# W026B.net
KiCad netlist of a schematic drawn in EAGLE
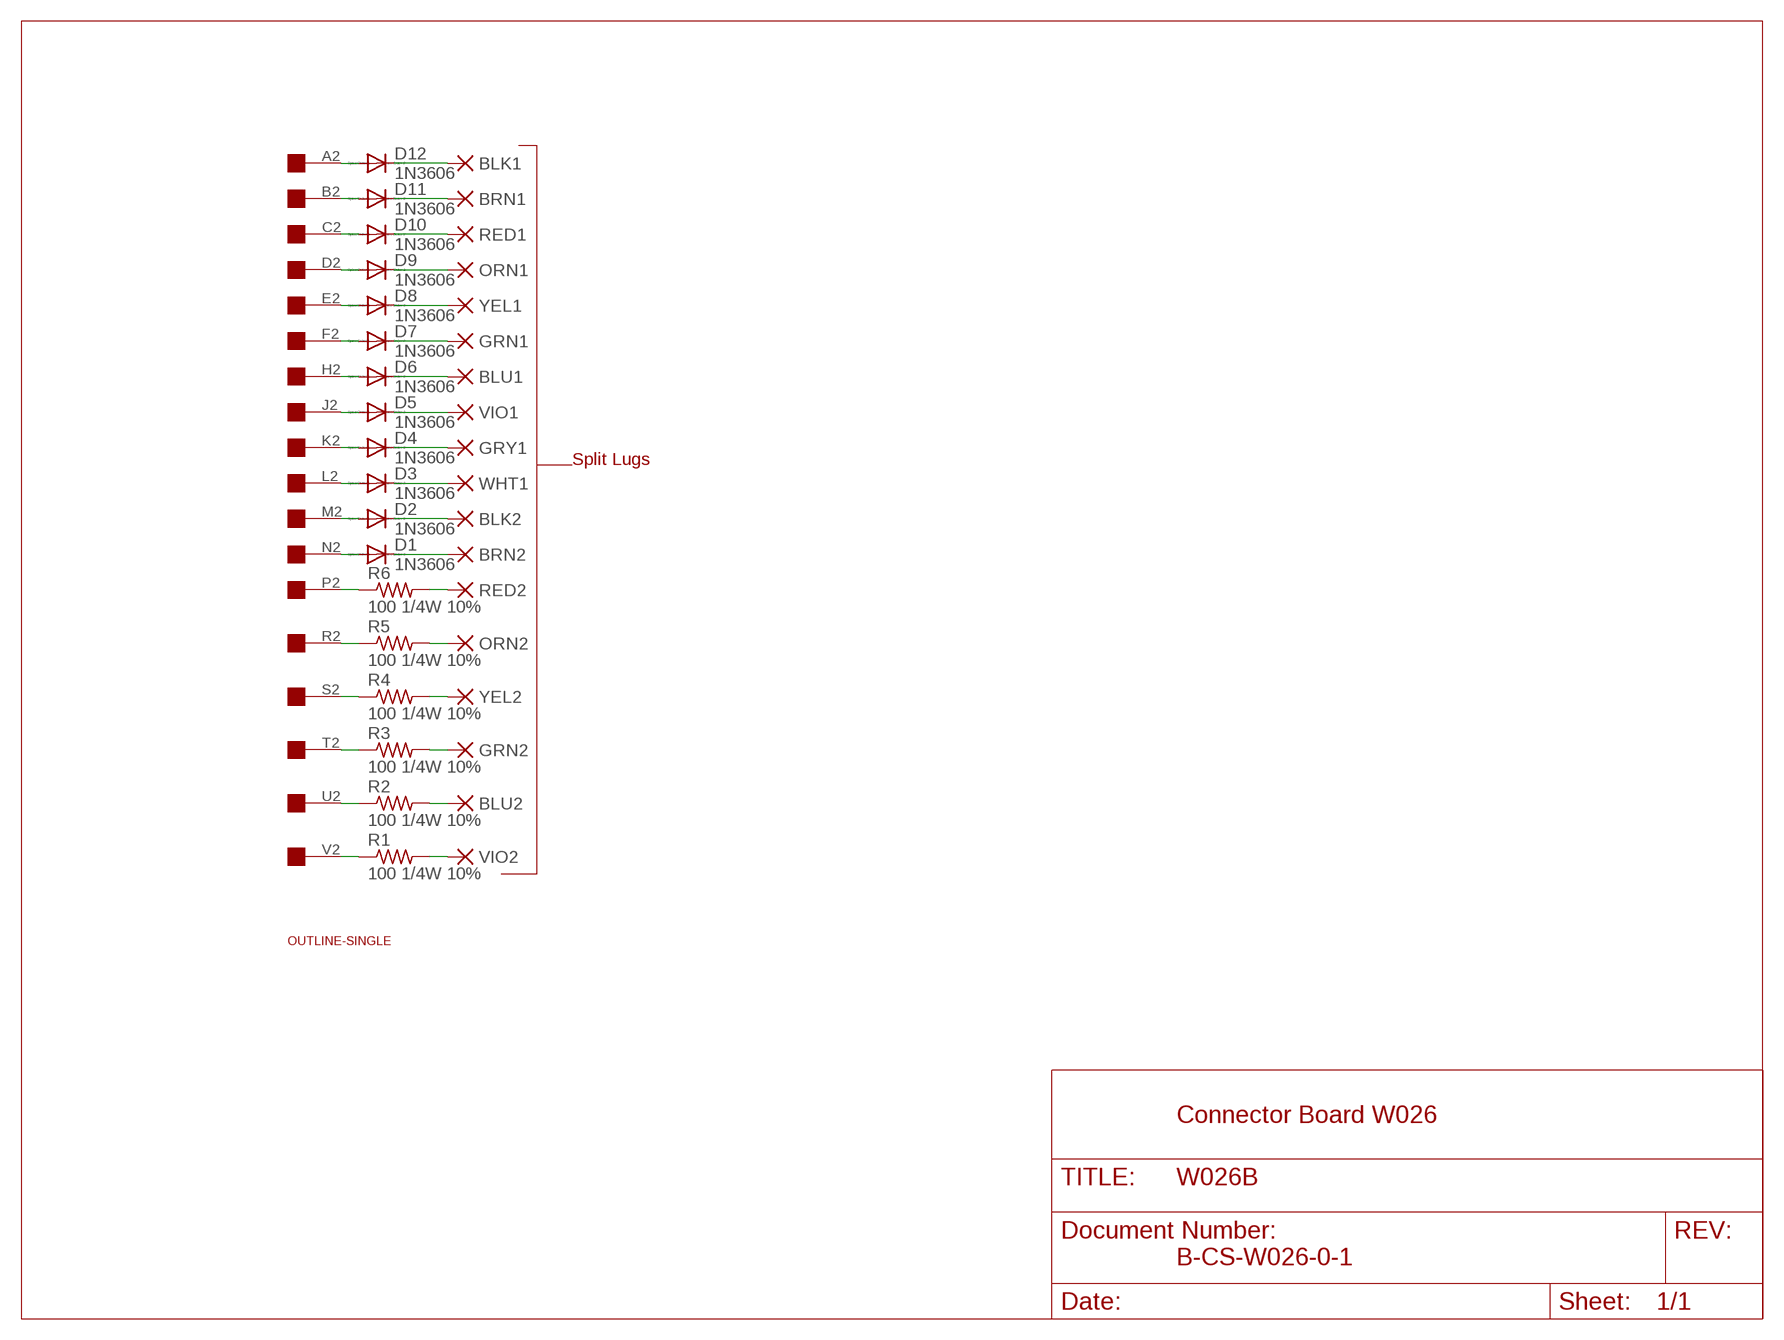
[diagram p0: schematic, sheet 1]

(export (version "E")
  (design (tool "Eeschema 10.0.6"))
  (components
    (comp (ref "BLK1")
      (value "PAD-0465")
      (footprint "eagle-import:0465")
      (libsource (lib "eagle-import") (part "PAD-0465"))
    )
    (comp (ref "BLK2")
      (value "PAD-0465")
      (footprint "eagle-import:0465")
      (libsource (lib "eagle-import") (part "PAD-0465"))
    )
    (comp (ref "BLU1")
      (value "PAD-0465")
      (footprint "eagle-import:0465")
      (libsource (lib "eagle-import") (part "PAD-0465"))
    )
    (comp (ref "BLU2")
      (value "PAD-0465")
      (footprint "eagle-import:0465")
      (libsource (lib "eagle-import") (part "PAD-0465"))
    )
    (comp (ref "BRN1")
      (value "PAD-0465")
      (footprint "eagle-import:0465")
      (libsource (lib "eagle-import") (part "PAD-0465"))
    )
    (comp (ref "BRN2")
      (value "PAD-0465")
      (footprint "eagle-import:0465")
      (libsource (lib "eagle-import") (part "PAD-0465"))
    )
    (comp (ref "D1")
      (value "1N3606")
      (footprint "eagle-import:DO35-10")
      (libsource (lib "eagle-import") (part "1N4148DO35-10"))
    )
    (comp (ref "D2")
      (value "1N3606")
      (footprint "eagle-import:DO35-10")
      (libsource (lib "eagle-import") (part "1N4148DO35-10"))
    )
    (comp (ref "D3")
      (value "1N3606")
      (footprint "eagle-import:DO35-10")
      (libsource (lib "eagle-import") (part "1N4148DO35-10"))
    )
    (comp (ref "D4")
      (value "1N3606")
      (footprint "eagle-import:DO35-10")
      (libsource (lib "eagle-import") (part "1N4148DO35-10"))
    )
    (comp (ref "D5")
      (value "1N3606")
      (footprint "eagle-import:DO35-10")
      (libsource (lib "eagle-import") (part "1N4148DO35-10"))
    )
    (comp (ref "D6")
      (value "1N3606")
      (footprint "eagle-import:DO35-10")
      (libsource (lib "eagle-import") (part "1N4148DO35-10"))
    )
    (comp (ref "D7")
      (value "1N3606")
      (footprint "eagle-import:DO35-10")
      (libsource (lib "eagle-import") (part "1N4148DO35-10"))
    )
    (comp (ref "D8")
      (value "1N3606")
      (footprint "eagle-import:DO35-10")
      (libsource (lib "eagle-import") (part "1N4148DO35-10"))
    )
    (comp (ref "D9")
      (value "1N3606")
      (footprint "eagle-import:DO35-10")
      (libsource (lib "eagle-import") (part "1N4148DO35-10"))
    )
    (comp (ref "D10")
      (value "1N3606")
      (footprint "eagle-import:DO35-10")
      (libsource (lib "eagle-import") (part "1N4148DO35-10"))
    )
    (comp (ref "D11")
      (value "1N3606")
      (footprint "eagle-import:DO35-10")
      (libsource (lib "eagle-import") (part "1N4148DO35-10"))
    )
    (comp (ref "D12")
      (value "1N3606")
      (footprint "eagle-import:DO35-10")
      (libsource (lib "eagle-import") (part "1N4148DO35-10"))
    )
    (comp (ref "GRN1")
      (value "PAD-0465")
      (footprint "eagle-import:0465")
      (libsource (lib "eagle-import") (part "PAD-0465"))
    )
    (comp (ref "GRN2")
      (value "PAD-0465")
      (footprint "eagle-import:0465")
      (libsource (lib "eagle-import") (part "PAD-0465"))
    )
    (comp (ref "GRY1")
      (value "PAD-0465")
      (footprint "eagle-import:0465")
      (libsource (lib "eagle-import") (part "PAD-0465"))
    )
    (comp (ref "ORN1")
      (value "PAD-0465")
      (footprint "eagle-import:0465")
      (libsource (lib "eagle-import") (part "PAD-0465"))
    )
    (comp (ref "ORN2")
      (value "PAD-0465")
      (footprint "eagle-import:0465")
      (libsource (lib "eagle-import") (part "PAD-0465"))
    )
    (comp (ref "R1")
      (value "100 1/4W 10%")
      (footprint "eagle-import:0207_10")
      (libsource (lib "eagle-import") (part "R-US_0207/10"))
    )
    (comp (ref "R2")
      (value "100 1/4W 10%")
      (footprint "eagle-import:0207_10")
      (libsource (lib "eagle-import") (part "R-US_0207/10"))
    )
    (comp (ref "R3")
      (value "100 1/4W 10%")
      (footprint "eagle-import:0207_10")
      (libsource (lib "eagle-import") (part "R-US_0207/10"))
    )
    (comp (ref "R4")
      (value "100 1/4W 10%")
      (footprint "eagle-import:0207_10")
      (libsource (lib "eagle-import") (part "R-US_0207/10"))
    )
    (comp (ref "R5")
      (value "100 1/4W 10%")
      (footprint "eagle-import:0207_10")
      (libsource (lib "eagle-import") (part "R-US_0207/10"))
    )
    (comp (ref "R6")
      (value "100 1/4W 10%")
      (footprint "eagle-import:0207_10")
      (libsource (lib "eagle-import") (part "R-US_0207/10"))
    )
    (comp (ref "RED1")
      (value "PAD-0465")
      (footprint "eagle-import:0465")
      (libsource (lib "eagle-import") (part "PAD-0465"))
    )
    (comp (ref "RED2")
      (value "PAD-0465")
      (footprint "eagle-import:0465")
      (libsource (lib "eagle-import") (part "PAD-0465"))
    )
    (comp (ref "U$1")
      (value "OUTLINE-SINGLE")
      (footprint "eagle-import:SINGLE")
      (libsource (lib "eagle-import") (part "OUTLINE-SINGLE"))
    )
    (comp (ref "U$2")
      (value "EDGE-1")
      (footprint "eagle-import:EDGE-CON1")
      (libsource (lib "eagle-import") (part "EDGE-1"))
    )
    (comp (ref "VIO1")
      (value "PAD-0465")
      (footprint "eagle-import:0465")
      (libsource (lib "eagle-import") (part "PAD-0465"))
    )
    (comp (ref "VIO2")
      (value "PAD-0465")
      (footprint "eagle-import:0465")
      (libsource (lib "eagle-import") (part "PAD-0465"))
    )
    (comp (ref "WHT1")
      (value "PAD-0465")
      (footprint "eagle-import:0465")
      (libsource (lib "eagle-import") (part "PAD-0465"))
    )
    (comp (ref "YEL1")
      (value "PAD-0465")
      (footprint "eagle-import:0465")
      (libsource (lib "eagle-import") (part "PAD-0465"))
    )
    (comp (ref "YEL2")
      (value "PAD-0465")
      (footprint "eagle-import:0465")
      (libsource (lib "eagle-import") (part "PAD-0465"))
    )
  )
  (nets
    (net (code "1") (name "Net-(BLK1-P)") (class "Default")
      (node (ref "BLK1") (pin "P$1") (pinfunction "P_P$1") (pintype "passive"))
      (node (ref "D12") (pin "C") (pinfunction "C_C") (pintype "passive"))
    )
    (net (code "2") (name "Net-(BLK2-P)") (class "Default")
      (node (ref "BLK2") (pin "P$1") (pinfunction "P_P$1") (pintype "passive"))
      (node (ref "D2") (pin "C") (pinfunction "C_C") (pintype "passive"))
    )
    (net (code "3") (name "Net-(BLU1-P)") (class "Default")
      (node (ref "BLU1") (pin "P$1") (pinfunction "P_P$1") (pintype "passive"))
      (node (ref "D6") (pin "C") (pinfunction "C_C") (pintype "passive"))
    )
    (net (code "4") (name "Net-(BLU2-P)") (class "Default")
      (node (ref "BLU2") (pin "P$1") (pinfunction "P_P$1") (pintype "passive"))
      (node (ref "R2") (pin "2") (pinfunction "2_2") (pintype "passive"))
    )
    (net (code "5") (name "Net-(BRN1-P)") (class "Default")
      (node (ref "BRN1") (pin "P$1") (pinfunction "P_P$1") (pintype "passive"))
      (node (ref "D11") (pin "C") (pinfunction "C_C") (pintype "passive"))
    )
    (net (code "6") (name "Net-(BRN2-P)") (class "Default")
      (node (ref "BRN2") (pin "P$1") (pinfunction "P_P$1") (pintype "passive"))
      (node (ref "D1") (pin "C") (pinfunction "C_C") (pintype "passive"))
    )
    (net (code "7") (name "Net-(GRN1-P)") (class "Default")
      (node (ref "D7") (pin "C") (pinfunction "C_C") (pintype "passive"))
      (node (ref "GRN1") (pin "P$1") (pinfunction "P_P$1") (pintype "passive"))
    )
    (net (code "8") (name "Net-(GRN2-P)") (class "Default")
      (node (ref "GRN2") (pin "P$1") (pinfunction "P_P$1") (pintype "passive"))
      (node (ref "R3") (pin "2") (pinfunction "2_2") (pintype "passive"))
    )
    (net (code "9") (name "Net-(GRY1-P)") (class "Default")
      (node (ref "D4") (pin "C") (pinfunction "C_C") (pintype "passive"))
      (node (ref "GRY1") (pin "P$1") (pinfunction "P_P$1") (pintype "passive"))
    )
    (net (code "10") (name "Net-(ORN1-P)") (class "Default")
      (node (ref "D9") (pin "C") (pinfunction "C_C") (pintype "passive"))
      (node (ref "ORN1") (pin "P$1") (pinfunction "P_P$1") (pintype "passive"))
    )
    (net (code "11") (name "Net-(ORN2-P)") (class "Default")
      (node (ref "ORN2") (pin "P$1") (pinfunction "P_P$1") (pintype "passive"))
      (node (ref "R5") (pin "2") (pinfunction "2_2") (pintype "passive"))
    )
    (net (code "12") (name "Net-(RED1-P)") (class "Default")
      (node (ref "D10") (pin "C") (pinfunction "C_C") (pintype "passive"))
      (node (ref "RED1") (pin "P$1") (pinfunction "P_P$1") (pintype "passive"))
    )
    (net (code "13") (name "Net-(RED2-P)") (class "Default")
      (node (ref "R6") (pin "2") (pinfunction "2_2") (pintype "passive"))
      (node (ref "RED2") (pin "P$1") (pinfunction "P_P$1") (pintype "passive"))
    )
    (net (code "14") (name "Net-(U$2A-1)") (class "Default")
      (node (ref "D12") (pin "A") (pinfunction "A_A") (pintype "passive"))
      (node (ref "U$2") (pin "A2") (pinfunction "1_A2") (pintype "bidirectional"))
    )
    (net (code "15") (name "Net-(U$2B-1)") (class "Default")
      (node (ref "D11") (pin "A") (pinfunction "A_A") (pintype "passive"))
      (node (ref "U$2") (pin "B2") (pinfunction "1_B2") (pintype "bidirectional"))
    )
    (net (code "16") (name "Net-(U$2C-1)") (class "Default")
      (node (ref "D10") (pin "A") (pinfunction "A_A") (pintype "passive"))
      (node (ref "U$2") (pin "C2") (pinfunction "1_C2") (pintype "bidirectional"))
    )
    (net (code "17") (name "Net-(U$2D-1)") (class "Default")
      (node (ref "D9") (pin "A") (pinfunction "A_A") (pintype "passive"))
      (node (ref "U$2") (pin "D2") (pinfunction "1_D2") (pintype "bidirectional"))
    )
    (net (code "18") (name "Net-(U$2E-1)") (class "Default")
      (node (ref "D8") (pin "A") (pinfunction "A_A") (pintype "passive"))
      (node (ref "U$2") (pin "E2") (pinfunction "1_E2") (pintype "bidirectional"))
    )
    (net (code "19") (name "Net-(U$2F-1)") (class "Default")
      (node (ref "D7") (pin "A") (pinfunction "A_A") (pintype "passive"))
      (node (ref "U$2") (pin "F2") (pinfunction "1_F2") (pintype "bidirectional"))
    )
    (net (code "20") (name "Net-(U$2G-1)") (class "Default")
      (node (ref "D6") (pin "A") (pinfunction "A_A") (pintype "passive"))
      (node (ref "U$2") (pin "H2") (pinfunction "1_H2") (pintype "bidirectional"))
    )
    (net (code "21") (name "Net-(U$2H-1)") (class "Default")
      (node (ref "D5") (pin "A") (pinfunction "A_A") (pintype "passive"))
      (node (ref "U$2") (pin "J2") (pinfunction "1_J2") (pintype "bidirectional"))
    )
    (net (code "22") (name "Net-(U$2I-1)") (class "Default")
      (node (ref "D4") (pin "A") (pinfunction "A_A") (pintype "passive"))
      (node (ref "U$2") (pin "K2") (pinfunction "1_K2") (pintype "bidirectional"))
    )
    (net (code "23") (name "Net-(U$2J-1)") (class "Default")
      (node (ref "D3") (pin "A") (pinfunction "A_A") (pintype "passive"))
      (node (ref "U$2") (pin "L2") (pinfunction "1_L2") (pintype "bidirectional"))
    )
    (net (code "24") (name "Net-(U$2K-1)") (class "Default")
      (node (ref "D2") (pin "A") (pinfunction "A_A") (pintype "passive"))
      (node (ref "U$2") (pin "M2") (pinfunction "1_M2") (pintype "bidirectional"))
    )
    (net (code "25") (name "Net-(U$2L-1)") (class "Default")
      (node (ref "D1") (pin "A") (pinfunction "A_A") (pintype "passive"))
      (node (ref "U$2") (pin "N2") (pinfunction "1_N2") (pintype "bidirectional"))
    )
    (net (code "26") (name "Net-(U$2M-1)") (class "Default")
      (node (ref "R6") (pin "1") (pinfunction "1_1") (pintype "passive"))
      (node (ref "U$2") (pin "P2") (pinfunction "1_P2") (pintype "bidirectional"))
    )
    (net (code "27") (name "Net-(U$2N-1)") (class "Default")
      (node (ref "R5") (pin "1") (pinfunction "1_1") (pintype "passive"))
      (node (ref "U$2") (pin "R2") (pinfunction "1_R2") (pintype "bidirectional"))
    )
    (net (code "28") (name "Net-(U$2O-1)") (class "Default")
      (node (ref "R4") (pin "1") (pinfunction "1_1") (pintype "passive"))
      (node (ref "U$2") (pin "S2") (pinfunction "1_S2") (pintype "bidirectional"))
    )
    (net (code "29") (name "Net-(U$2P-1)") (class "Default")
      (node (ref "R3") (pin "1") (pinfunction "1_1") (pintype "passive"))
      (node (ref "U$2") (pin "T2") (pinfunction "1_T2") (pintype "bidirectional"))
    )
    (net (code "30") (name "Net-(U$2Q-1)") (class "Default")
      (node (ref "R2") (pin "1") (pinfunction "1_1") (pintype "passive"))
      (node (ref "U$2") (pin "U2") (pinfunction "1_U2") (pintype "bidirectional"))
    )
    (net (code "31") (name "Net-(U$2R-1)") (class "Default")
      (node (ref "R1") (pin "1") (pinfunction "1_1") (pintype "passive"))
      (node (ref "U$2") (pin "V2") (pinfunction "1_V2") (pintype "bidirectional"))
    )
    (net (code "32") (name "Net-(VIO1-P)") (class "Default")
      (node (ref "D5") (pin "C") (pinfunction "C_C") (pintype "passive"))
      (node (ref "VIO1") (pin "P$1") (pinfunction "P_P$1") (pintype "passive"))
    )
    (net (code "33") (name "Net-(VIO2-P)") (class "Default")
      (node (ref "R1") (pin "2") (pinfunction "2_2") (pintype "passive"))
      (node (ref "VIO2") (pin "P$1") (pinfunction "P_P$1") (pintype "passive"))
    )
    (net (code "34") (name "Net-(WHT1-P)") (class "Default")
      (node (ref "D3") (pin "C") (pinfunction "C_C") (pintype "passive"))
      (node (ref "WHT1") (pin "P$1") (pinfunction "P_P$1") (pintype "passive"))
    )
    (net (code "35") (name "Net-(YEL1-P)") (class "Default")
      (node (ref "D8") (pin "C") (pinfunction "C_C") (pintype "passive"))
      (node (ref "YEL1") (pin "P$1") (pinfunction "P_P$1") (pintype "passive"))
    )
    (net (code "36") (name "Net-(YEL2-P)") (class "Default")
      (node (ref "R4") (pin "2") (pinfunction "2_2") (pintype "passive"))
      (node (ref "YEL2") (pin "P$1") (pinfunction "P_P$1") (pintype "passive"))
    )
  )
)
